# STM32.net
KiCad netlist of a schematic drawn in Altium Designer
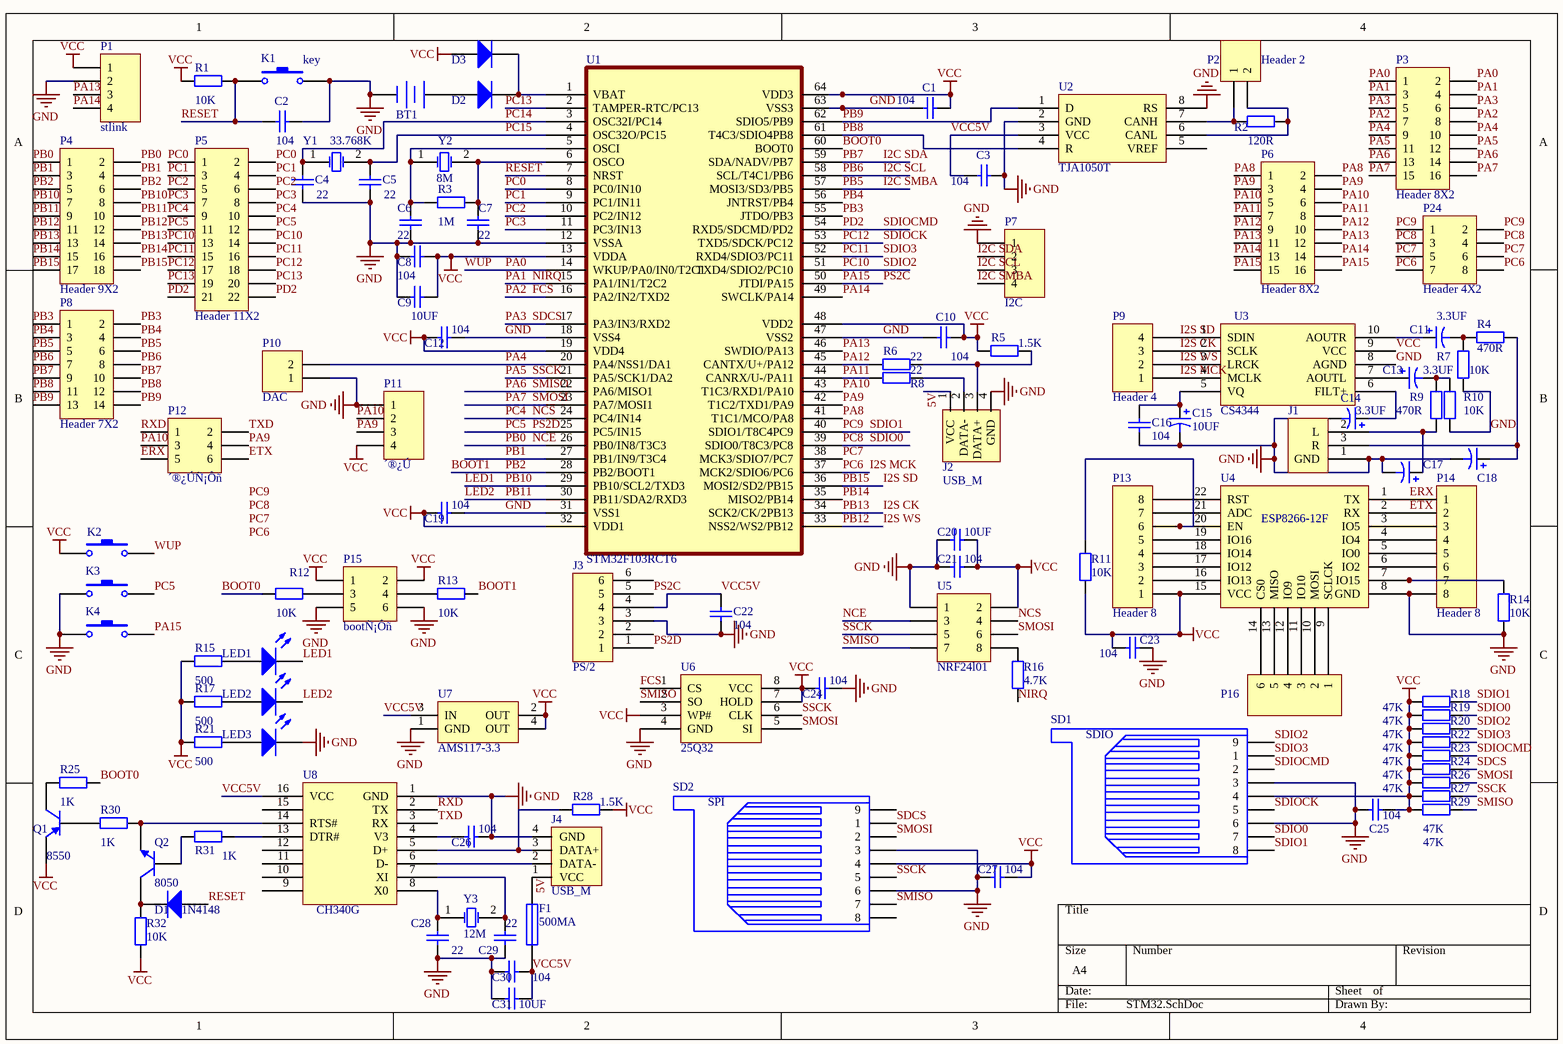
[diagram p0: STM32.SchDoc]

(export (version "E")
  (design (tool "Eeschema 10.0.6"))
  (components
    (comp (ref "BT1") (value "电池") (footprint "电池座") (libsource (lib "SCH封装库") (part "电池")))
    (comp (ref "C1")
      (value "104")
      (footprint "6-0805_N")
      (description "Capacitor")
      (fields (field (name "Comment") "Cap") (field (name "PUBLISHER") "Altium Limited"))
      (libsource (lib "Miscellaneous Devices") (part "Cap"))
    )
    (comp (ref "C2")
      (value "104")
      (footprint "6-0805_N")
      (description "Capacitor")
      (fields (field (name "Comment") "Cap") (field (name "PUBLISHER") "Altium Limited"))
      (libsource (lib "Miscellaneous Devices") (part "Cap"))
    )
    (comp (ref "C3")
      (value "104")
      (footprint "6-0805_N")
      (description "Capacitor")
      (fields (field (name "Comment") "Cap") (field (name "PUBLISHER") "Altium Limited"))
      (libsource (lib "Miscellaneous Devices") (part "Cap"))
    )
    (comp (ref "C4")
      (value "22")
      (footprint "6-0805_N")
      (description "Capacitor")
      (fields (field (name "Comment") "Cap") (field (name "PUBLISHER") "Altium Limited"))
      (libsource (lib "Miscellaneous Devices") (part "Cap"))
    )
    (comp (ref "C5")
      (value "22")
      (footprint "6-0805_N")
      (description "Capacitor")
      (fields (field (name "Comment") "Cap") (field (name "PUBLISHER") "Altium Limited"))
      (libsource (lib "Miscellaneous Devices") (part "Cap"))
    )
    (comp (ref "C6")
      (value "22")
      (footprint "6-0805_N")
      (description "Capacitor")
      (fields (field (name "Comment") "Cap") (field (name "PUBLISHER") "Altium Limited"))
      (libsource (lib "Miscellaneous Devices") (part "Cap"))
    )
    (comp (ref "C7")
      (value "22")
      (footprint "6-0805_N")
      (description "Capacitor")
      (fields (field (name "Comment") "Cap") (field (name "PUBLISHER") "Altium Limited"))
      (libsource (lib "Miscellaneous Devices") (part "Cap"))
    )
    (comp (ref "C8")
      (value "104")
      (footprint "6-0805_N")
      (description "Capacitor")
      (fields (field (name "Comment") "Cap") (field (name "PUBLISHER") "Altium Limited"))
      (libsource (lib "Miscellaneous Devices") (part "Cap"))
    )
    (comp (ref "C9")
      (value "10UF")
      (footprint "6-0805_N")
      (description "Capacitor")
      (fields (field (name "Comment") "Cap") (field (name "PUBLISHER") "Altium Limited"))
      (libsource (lib "Miscellaneous Devices") (part "Cap"))
    )
    (comp (ref "C10")
      (value "104")
      (footprint "6-0805_N")
      (description "Capacitor")
      (fields (field (name "Comment") "Cap") (field (name "PUBLISHER") "Altium Limited"))
      (libsource (lib "Miscellaneous Devices") (part "Cap"))
    )
    (comp (ref "C11")
      (value "3.3UF")
      (footprint "极性电容")
      (description "Polarized Capacitor (Surface Mount)")
      (fields (field (name "Comment") "Cap Pol3") (field (name "PUBLISHER") "Altium Limited"))
      (libsource (lib "Miscellaneous Devices") (part "Cap Pol3"))
    )
    (comp (ref "C12")
      (value "104")
      (footprint "6-0805_N")
      (description "Capacitor")
      (fields (field (name "Comment") "Cap") (field (name "PUBLISHER") "Altium Limited"))
      (libsource (lib "Miscellaneous Devices") (part "Cap"))
    )
    (comp (ref "C13")
      (value "3.3UF")
      (footprint "极性电容")
      (description "Polarized Capacitor (Surface Mount)")
      (fields (field (name "Comment") "Cap Pol3") (field (name "PUBLISHER") "Altium Limited"))
      (libsource (lib "Miscellaneous Devices") (part "Cap Pol3"))
    )
    (comp (ref "C14")
      (value "3.3UF")
      (footprint "极性电容")
      (description "Polarized Capacitor (Surface Mount)")
      (fields (field (name "Comment") "Cap Pol3") (field (name "PUBLISHER") "Altium Limited"))
      (libsource (lib "Miscellaneous Devices") (part "Cap Pol3"))
    )
    (comp (ref "C15")
      (value "10UF")
      (footprint "极性电容")
      (description "Polarized Capacitor (Surface Mount)")
      (fields (field (name "Comment") "Cap Pol3") (field (name "PUBLISHER") "Altium Limited"))
      (libsource (lib "Miscellaneous Devices") (part "Cap Pol3"))
    )
    (comp (ref "C16")
      (value "104")
      (footprint "6-0805_N")
      (description "Capacitor")
      (fields (field (name "Comment") "Cap") (field (name "PUBLISHER") "Altium Limited"))
      (libsource (lib "Miscellaneous Devices") (part "Cap"))
    )
    (comp (ref "C17")
      (value "Cap Pol3")
      (footprint "极性电容")
      (description "Polarized Capacitor (Surface Mount)")
      (fields (field (name "PUBLISHER") "Altium Limited"))
      (libsource (lib "Miscellaneous Devices") (part "Cap Pol3"))
    )
    (comp (ref "C18")
      (value "Cap Pol3")
      (footprint "极性电容")
      (description "Polarized Capacitor (Surface Mount)")
      (fields (field (name "PUBLISHER") "Altium Limited"))
      (libsource (lib "Miscellaneous Devices") (part "Cap Pol3"))
    )
    (comp (ref "C19")
      (value "104")
      (footprint "6-0805_N")
      (description "Capacitor")
      (fields (field (name "Comment") "Cap") (field (name "PUBLISHER") "Altium Limited"))
      (libsource (lib "Miscellaneous Devices") (part "Cap"))
    )
    (comp (ref "C20")
      (value "10UF")
      (footprint "6-0805_N")
      (description "Capacitor")
      (fields (field (name "Comment") "Cap") (field (name "PUBLISHER") "Altium Limited"))
      (libsource (lib "Miscellaneous Devices") (part "Cap"))
    )
    (comp (ref "C21")
      (value "104")
      (footprint "6-0805_N")
      (description "Capacitor")
      (fields (field (name "Comment") "Cap") (field (name "PUBLISHER") "Altium Limited"))
      (libsource (lib "Miscellaneous Devices") (part "Cap"))
    )
    (comp (ref "C22")
      (value "104")
      (footprint "6-0805_N")
      (description "Capacitor")
      (fields (field (name "Comment") "Cap") (field (name "PUBLISHER") "Altium Limited"))
      (libsource (lib "Miscellaneous Devices") (part "Cap"))
    )
    (comp (ref "C23")
      (value "104")
      (footprint "6-0805_N")
      (description "Capacitor")
      (fields (field (name "Comment") "Cap") (field (name "PUBLISHER") "Altium Limited"))
      (libsource (lib "Miscellaneous Devices") (part "Cap"))
    )
    (comp (ref "C24")
      (value "104")
      (footprint "6-0805_N")
      (description "Capacitor")
      (fields (field (name "Comment") "Cap") (field (name "PUBLISHER") "Altium Limited"))
      (libsource (lib "Miscellaneous Devices") (part "Cap"))
    )
    (comp (ref "C25")
      (value "104")
      (footprint "6-0805_N")
      (description "Capacitor")
      (fields (field (name "Comment") "Cap") (field (name "PUBLISHER") "Altium Limited"))
      (libsource (lib "Miscellaneous Devices") (part "Cap"))
    )
    (comp (ref "C26")
      (value "104")
      (footprint "6-0805_N")
      (description "Capacitor")
      (fields (field (name "Comment") "Cap") (field (name "PUBLISHER") "Altium Limited"))
      (libsource (lib "Miscellaneous Devices") (part "Cap"))
    )
    (comp (ref "C27")
      (value "104")
      (footprint "6-0805_N")
      (description "Capacitor")
      (fields (field (name "Comment") "Cap") (field (name "PUBLISHER") "Altium Limited"))
      (libsource (lib "Miscellaneous Devices") (part "Cap"))
    )
    (comp (ref "C28")
      (value "22")
      (footprint "6-0805_N")
      (description "Capacitor")
      (fields (field (name "Comment") "Cap") (field (name "PUBLISHER") "Altium Limited"))
      (libsource (lib "Miscellaneous Devices") (part "Cap"))
    )
    (comp (ref "C29")
      (value "22")
      (footprint "6-0805_N")
      (description "Capacitor")
      (fields (field (name "Comment") "Cap") (field (name "PUBLISHER") "Altium Limited"))
      (libsource (lib "Miscellaneous Devices") (part "Cap"))
    )
    (comp (ref "C30")
      (value "104")
      (footprint "6-0805_N")
      (description "Capacitor")
      (fields (field (name "Comment") "Cap") (field (name "PUBLISHER") "Altium Limited"))
      (libsource (lib "Miscellaneous Devices") (part "Cap"))
    )
    (comp (ref "C31")
      (value "10UF")
      (footprint "6-0805_N")
      (description "Capacitor")
      (fields (field (name "Comment") "Cap") (field (name "PUBLISHER") "Altium Limited"))
      (libsource (lib "Miscellaneous Devices") (part "Cap"))
    )
    (comp (ref "D1")
      (value "1N4148")
      (footprint "1206")
      (description "High Conductance Fast Diode")
      (fields (field (name "PUBLISHER") "Altium Limited"))
      (libsource (lib "Miscellaneous Devices") (part "Diode 1N4148"))
    )
    (comp (ref "D2")
      (value "1N4148")
      (footprint "1206")
      (description "High Conductance Fast Diode")
      (fields (field (name "PUBLISHER") "Altium Limited"))
      (libsource (lib "Miscellaneous Devices") (part "Diode 1N4148"))
    )
    (comp (ref "D3")
      (value "1N4148")
      (footprint "1206")
      (description "High Conductance Fast Diode")
      (fields (field (name "PUBLISHER") "Altium Limited"))
      (libsource (lib "Miscellaneous Devices") (part "Diode 1N4148"))
    )
    (comp (ref "F1")
      (value "500MA")
      (footprint "1812")
      (description "Fuse")
      (fields (field (name "PUBLISHER") "Altium Limited"))
      (libsource (lib "Miscellaneous Devices") (part "Fuse 1"))
    )
    (comp (ref "J1") (value "Component_1") (footprint "耳机座") (libsource (lib "耳机") (part "Component_1")))
    (comp (ref "J2") (value "USB_M") (footprint "USB MICRO") (libsource (lib "") (part "USB_M_1")))
    (comp (ref "J3") (value "PS/2") (footprint "PS/2") (libsource (lib "SCH封装库") (part "PS/2")))
    (comp (ref "J4") (value "USB_M") (footprint "USB MICRO") (libsource (lib "SCH封装库") (part "USB_M")))
    (comp (ref "K1") (value "key") (footprint "按键") (libsource (lib "SCH封装库") (part "按键")))
    (comp (ref "K2") (value "按键") (footprint "按键") (libsource (lib "SCH封装库") (part "按键")))
    (comp (ref "K3") (value "按键") (footprint "按键") (libsource (lib "SCH封装库") (part "按键")))
    (comp (ref "K4") (value "按键") (footprint "按键") (libsource (lib "SCH封装库") (part "按键")))
    (comp (ref "LED1") (value "LED") (footprint "6-0805_N") (libsource (lib "SCH封装库") (part "发光二极管")))
    (comp (ref "LED2") (value "LED") (footprint "6-0805_N") (libsource (lib "SCH封装库") (part "发光二极管")))
    (comp (ref "LED3") (value "LED") (footprint "6-0805_N") (libsource (lib "SCH封装库") (part "发光二极管")))
    (comp (ref "P1")
      (value "stlink")
      (footprint "HDR1X4")
      (description "Header, 4-Pin")
      (fields (field (name "PUBLISHER") "Altium Limited"))
      (libsource (lib "") (part "Header 4_1"))
    )
    (comp (ref "P2")
      (value "Header 2")
      (footprint "HDR1X2")
      (description "Header, 2-Pin")
      (fields (field (name "PUBLISHER") "Altium Limited"))
      (libsource (lib "") (part "Header 2_1"))
    )
    (comp (ref "P3")
      (value "Header 8X2")
      (footprint "HDR2X8")
      (description "Header, 8-Pin, Dual row")
      (fields (field (name "PUBLISHER") "Altium Limited"))
      (libsource (lib "Miscellaneous Connectors") (part "Header 8X2"))
    )
    (comp (ref "P4")
      (value "Header 9X2")
      (footprint "HDR2X9")
      (description "Header, 9-Pin, Dual row")
      (fields (field (name "PUBLISHER") "Altium Limited"))
      (libsource (lib "Miscellaneous Connectors") (part "Header 9X2"))
    )
    (comp (ref "P5")
      (value "Header 11X2")
      (footprint "HDR2X11")
      (description "Header, 11-Pin, Dual row")
      (fields (field (name "PUBLISHER") "Altium Limited"))
      (libsource (lib "Miscellaneous Connectors") (part "Header 11X2"))
    )
    (comp (ref "P6")
      (value "Header 8X2")
      (footprint "HDR2X8")
      (description "Header, 8-Pin, Dual row")
      (fields (field (name "PUBLISHER") "Altium Limited"))
      (libsource (lib "Miscellaneous Connectors") (part "Header 8X2"))
    )
    (comp (ref "P7")
      (value "I2C")
      (footprint "HDR1X4")
      (description "Header, 4-Pin")
      (fields (field (name "PUBLISHER") "Altium Limited"))
      (libsource (lib "") (part "Header 4_1"))
    )
    (comp (ref "P8")
      (value "Header 7X2")
      (footprint "HDR2X7")
      (description "Header, 7-Pin, Dual row")
      (fields (field (name "PUBLISHER") "Altium Limited"))
      (libsource (lib "Miscellaneous Connectors") (part "Header 7X2"))
    )
    (comp (ref "P9")
      (value "Header 4")
      (footprint "HDR1X4")
      (description "Header, 4-Pin")
      (fields (field (name "PUBLISHER") "Altium Limited"))
      (libsource (lib "Miscellaneous Connectors") (part "Header 4"))
    )
    (comp (ref "P10")
      (value "DAC")
      (footprint "HDR1X2")
      (description "Header, 2-Pin")
      (fields (field (name "PUBLISHER") "Altium Limited"))
      (libsource (lib "Miscellaneous Connectors") (part "Header 2"))
    )
    (comp (ref "P11")
      (value "串口")
      (footprint "HDR1X4")
      (description "Header, 4-Pin")
      (fields (field (name "PUBLISHER") "Altium Limited"))
      (libsource (lib "") (part "Header 4_1"))
    )
    (comp (ref "P12")
      (value "串口选择")
      (footprint "HDR2X3")
      (description "Header, 3-Pin, Dual row")
      (fields (field (name "PUBLISHER") "Altium Limited"))
      (libsource (lib "Miscellaneous Connectors") (part "Header 3X2"))
    )
    (comp (ref "P13")
      (value "Header 8")
      (footprint "HDR1X8")
      (description "Header, 8-Pin")
      (fields (field (name "PUBLISHER") "Altium Limited"))
      (libsource (lib "") (part "Header 8_1"))
    )
    (comp (ref "P14")
      (value "Header 8")
      (footprint "HDR1X8")
      (description "Header, 8-Pin")
      (fields (field (name "PUBLISHER") "Altium Limited"))
      (libsource (lib "Miscellaneous Connectors") (part "Header 8"))
    )
    (comp (ref "P15")
      (value "boot选择")
      (footprint "HDR2X3")
      (description "Header, 3-Pin, Dual row")
      (fields (field (name "PUBLISHER") "Altium Limited"))
      (libsource (lib "Miscellaneous Connectors") (part "Header 3X2"))
    )
    (comp (ref "P16")
      (value "Header 6")
      (footprint "HDR1X6")
      (description "Header, 6-Pin")
      (fields (field (name "PUBLISHER") "Altium Limited"))
      (libsource (lib "Miscellaneous Connectors") (part "Header 6"))
    )
    (comp (ref "P24")
      (value "Header 4X2")
      (footprint "HDR2X4")
      (description "Header, 4-Pin, Dual row")
      (fields (field (name "PUBLISHER") "Altium Limited"))
      (libsource (lib "Miscellaneous Connectors") (part "Header 4X2"))
    )
    (comp (ref "Q1")
      (value "8550")
      (footprint "SOT-23B_N")
      (description "PNP Bipolar Transistor")
      (fields (field (name "PUBLISHER") "Altium Limited"))
      (libsource (lib "Miscellaneous Devices") (part "PNP"))
    )
    (comp (ref "Q2")
      (value "8050")
      (footprint "SOT-23B_N")
      (description "NPN Bipolar Transistor")
      (fields (field (name "PUBLISHER") "Altium Limited"))
      (libsource (lib "Miscellaneous Devices") (part "NPN"))
    )
    (comp (ref "R1")
      (value "10K")
      (footprint "6-0805_N")
      (description "Resistor")
      (fields (field (name "Comment") "Res2") (field (name "PUBLISHER") "Altium Limited"))
      (libsource (lib "Miscellaneous Devices") (part "Res2"))
    )
    (comp (ref "R2")
      (value "120R")
      (footprint "6-0805_N")
      (description "Resistor")
      (fields (field (name "Comment") "Res2") (field (name "PUBLISHER") "Altium Limited"))
      (libsource (lib "Miscellaneous Devices") (part "Res2"))
    )
    (comp (ref "R3")
      (value "1M")
      (footprint "6-0805_N")
      (description "Resistor")
      (fields (field (name "Comment") "Res2") (field (name "PUBLISHER") "Altium Limited"))
      (libsource (lib "Miscellaneous Devices") (part "Res2"))
    )
    (comp (ref "R4")
      (value "470R")
      (footprint "6-0805_N")
      (description "Resistor")
      (fields (field (name "Comment") "Res2") (field (name "PUBLISHER") "Altium Limited"))
      (libsource (lib "") (part "Res2_3"))
    )
    (comp (ref "R5")
      (value "1.5K")
      (footprint "6-0805_N")
      (description "Resistor")
      (fields (field (name "Comment") "Res2") (field (name "PUBLISHER") "Altium Limited"))
      (libsource (lib "Miscellaneous Devices") (part "Res2"))
    )
    (comp (ref "R6")
      (value "22")
      (footprint "6-0805_N")
      (description "Resistor")
      (fields (field (name "Comment") "Res2") (field (name "PUBLISHER") "Altium Limited"))
      (libsource (lib "Miscellaneous Devices") (part "Res2"))
    )
    (comp (ref "R7")
      (value "10K")
      (footprint "6-0805_N")
      (description "Resistor")
      (fields (field (name "Comment") "Res2") (field (name "PUBLISHER") "Altium Limited"))
      (libsource (lib "") (part "Res2_1"))
    )
    (comp (ref "R8")
      (value "22")
      (footprint "6-0805_N")
      (description "Resistor")
      (fields (field (name "Comment") "Res2") (field (name "PUBLISHER") "Altium Limited"))
      (libsource (lib "Miscellaneous Devices") (part "Res2"))
    )
    (comp (ref "R9")
      (value "470R")
      (footprint "6-0805_N")
      (description "Resistor")
      (fields (field (name "Comment") "Res2") (field (name "PUBLISHER") "Altium Limited"))
      (libsource (lib "") (part "Res2_2"))
    )
    (comp (ref "R10")
      (value "10K")
      (footprint "6-0805_N")
      (description "Resistor")
      (fields (field (name "Comment") "Res2") (field (name "PUBLISHER") "Altium Limited"))
      (libsource (lib "") (part "Res2_1"))
    )
    (comp (ref "R11")
      (value "10K")
      (footprint "6-0805_N")
      (description "Resistor")
      (fields (field (name "Comment") "Res2") (field (name "PUBLISHER") "Altium Limited"))
      (libsource (lib "") (part "Res2_1"))
    )
    (comp (ref "R12")
      (value "10K")
      (footprint "6-0805_N")
      (description "Resistor")
      (fields (field (name "Comment") "Res2") (field (name "PUBLISHER") "Altium Limited"))
      (libsource (lib "Miscellaneous Devices") (part "Res2"))
    )
    (comp (ref "R13")
      (value "10K")
      (footprint "6-0805_N")
      (description "Resistor")
      (fields (field (name "Comment") "Res2") (field (name "PUBLISHER") "Altium Limited"))
      (libsource (lib "Miscellaneous Devices") (part "Res2"))
    )
    (comp (ref "R14")
      (value "10K")
      (footprint "6-0805_N")
      (description "Resistor")
      (fields (field (name "Comment") "Res2") (field (name "PUBLISHER") "Altium Limited"))
      (libsource (lib "") (part "Res2_1"))
    )
    (comp (ref "R15")
      (value "500")
      (footprint "6-0805_N")
      (description "Resistor")
      (fields (field (name "Comment") "Res2") (field (name "PUBLISHER") "Altium Limited"))
      (libsource (lib "Miscellaneous Devices") (part "Res2"))
    )
    (comp (ref "R16")
      (value "4.7K")
      (footprint "6-0805_N")
      (description "Resistor")
      (fields (field (name "Comment") "Res2") (field (name "PUBLISHER") "Altium Limited"))
      (libsource (lib "") (part "Res2_2"))
    )
    (comp (ref "R17")
      (value "500")
      (footprint "6-0805_N")
      (description "Resistor")
      (fields (field (name "Comment") "Res2") (field (name "PUBLISHER") "Altium Limited"))
      (libsource (lib "Miscellaneous Devices") (part "Res2"))
    )
    (comp (ref "R18")
      (value "47K")
      (footprint "6-0805_N")
      (description "Resistor")
      (fields (field (name "Comment") "Res2") (field (name "PUBLISHER") "Altium Limited"))
      (libsource (lib "Miscellaneous Devices") (part "Res2"))
    )
    (comp (ref "R19")
      (value "47K")
      (footprint "6-0805_N")
      (description "Resistor")
      (fields (field (name "Comment") "Res2") (field (name "PUBLISHER") "Altium Limited"))
      (libsource (lib "Miscellaneous Devices") (part "Res2"))
    )
    (comp (ref "R20")
      (value "47K")
      (footprint "6-0805_N")
      (description "Resistor")
      (fields (field (name "Comment") "Res2") (field (name "PUBLISHER") "Altium Limited"))
      (libsource (lib "Miscellaneous Devices") (part "Res2"))
    )
    (comp (ref "R21")
      (value "500")
      (footprint "6-0805_N")
      (description "Resistor")
      (fields (field (name "Comment") "Res2") (field (name "PUBLISHER") "Altium Limited"))
      (libsource (lib "Miscellaneous Devices") (part "Res2"))
    )
    (comp (ref "R22")
      (value "47K")
      (footprint "6-0805_N")
      (description "Resistor")
      (fields (field (name "Comment") "Res2") (field (name "PUBLISHER") "Altium Limited"))
      (libsource (lib "Miscellaneous Devices") (part "Res2"))
    )
    (comp (ref "R23")
      (value "47K")
      (footprint "6-0805_N")
      (description "Resistor")
      (fields (field (name "Comment") "Res2") (field (name "PUBLISHER") "Altium Limited"))
      (libsource (lib "Miscellaneous Devices") (part "Res2"))
    )
    (comp (ref "R24")
      (value "47K")
      (footprint "6-0805_N")
      (description "Resistor")
      (fields (field (name "Comment") "Res2") (field (name "PUBLISHER") "Altium Limited"))
      (libsource (lib "Miscellaneous Devices") (part "Res2"))
    )
    (comp (ref "R25")
      (value "1K")
      (footprint "6-0805_N")
      (description "Resistor")
      (fields (field (name "Comment") "Res2") (field (name "PUBLISHER") "Altium Limited"))
      (libsource (lib "Miscellaneous Devices") (part "Res2"))
    )
    (comp (ref "R26")
      (value "47K")
      (footprint "6-0805_N")
      (description "Resistor")
      (fields (field (name "Comment") "Res2") (field (name "PUBLISHER") "Altium Limited"))
      (libsource (lib "Miscellaneous Devices") (part "Res2"))
    )
    (comp (ref "R27")
      (value "47K")
      (footprint "6-0805_N")
      (description "Resistor")
      (fields (field (name "Comment") "Res2") (field (name "PUBLISHER") "Altium Limited"))
      (libsource (lib "Miscellaneous Devices") (part "Res2"))
    )
    (comp (ref "R28")
      (value "1.5K")
      (footprint "6-0805_N")
      (description "Resistor")
      (fields (field (name "Comment") "Res2") (field (name "PUBLISHER") "Altium Limited"))
      (libsource (lib "Miscellaneous Devices") (part "Res2"))
    )
    (comp (ref "R29")
      (value "47K")
      (footprint "6-0805_N")
      (description "Resistor")
      (fields (field (name "Comment") "Res2") (field (name "PUBLISHER") "Altium Limited"))
      (libsource (lib "Miscellaneous Devices") (part "Res2"))
    )
    (comp (ref "R30")
      (value "1K")
      (footprint "6-0805_N")
      (description "Resistor")
      (fields (field (name "Comment") "Res2") (field (name "PUBLISHER") "Altium Limited"))
      (libsource (lib "Miscellaneous Devices") (part "Res2"))
    )
    (comp (ref "R31")
      (value "1K")
      (footprint "6-0805_N")
      (description "Resistor")
      (fields (field (name "Comment") "Res2") (field (name "PUBLISHER") "Altium Limited"))
      (libsource (lib "Miscellaneous Devices") (part "Res2"))
    )
    (comp (ref "R32")
      (value "10K")
      (footprint "6-0805_N")
      (description "Resistor")
      (fields (field (name "Comment") "Res2") (field (name "PUBLISHER") "Altium Limited"))
      (libsource (lib "") (part "Res2_1"))
    )
    (comp (ref "SD1")
      (value "PJS008-2000")
      (footprint "TFCARD-M")
      (fields (field (name "A") "SDIO"))
      (libsource (lib "MB525") (part "SMS016AFA5E"))
    )
    (comp (ref "SD2")
      (value "PJS008-2000")
      (footprint "SDCARD_A")
      (fields (field (name "A") "SPI"))
      (libsource (lib "MB525") (part "SMS016AFA5E"))
    )
    (comp (ref "U1")
      (value "STM32F103RCT6")
      (footprint "LQFP64")
      (libsource (lib "STM32SCH") (part "STM32F103RDT6"))
    )
    (comp (ref "U2") (value "TJA1050T") (footprint "SO8_M") (libsource (lib "TJA1050") (part "Component_1")))
    (comp (ref "U3")
      (value "CS4344")
      (footprint "TSSOP110_s")
      (libsource (lib "CS4344") (part "Component_1"))
    )
    (comp (ref "U4")
      (value "Component_1")
      (footprint "ESP_12_f")
      (libsource (lib "ESP8266") (part "Component_1"))
    )
    (comp (ref "U5")
      (value "NRF24l01")
      (footprint "HDR2X4")
      (description "Header, 4-Pin, Dual row")
      (fields (field (name "PUBLISHER") "Altium Limited"))
      (libsource (lib "Miscellaneous Connectors") (part "Header 4X2"))
    )
    (comp (ref "U6") (value "25Q32") (footprint "SO8_M") (libsource (lib "25Q32") (part "Component_1")))
    (comp (ref "U7")
      (value "AMS117-3.3")
      (footprint "ZZ311")
      (description "800mA and 1A Low Dropout Positive Regulator 2.85V, 3.3V, 5V, and Adjustable")
      (fields (field (name "PUBLISHER") "Altium Limited"))
      (libsource (lib "BB Power Mgt Voltage Regulator") (part "REG1117-3.3"))
    )
    (comp (ref "U8")
      (value "Component_1")
      (footprint "SO-16_M")
      (libsource (lib "CH340") (part "Component_1"))
    )
    (comp (ref "Y1") (value "33.768K") (footprint "SIP2") (libsource (lib "SCH封装库") (part "晶振")))
    (comp (ref "Y2") (value "8M") (footprint "晶振") (libsource (lib "SCH封装库") (part "晶振")))
    (comp (ref "Y3") (value "12M") (footprint "晶振") (libsource (lib "SCH封装库") (part "晶振")))
  )
  (nets
    (net (code "1") (name "/5V") (class "Default")
      (node (ref "F1") (pin "2") (pinfunction "2_2") (pintype "passive"))
      (node (ref "J2") (pin "1") (pinfunction "VCC_1") (pintype "passive"))
      (node (ref "J4") (pin "1") (pinfunction "VCC_1") (pintype "passive"))
    )
    (net (code "2") (name "/BOOT0") (class "Default")
      (node (ref "R12") (pin "1") (pinfunction "1_1") (pintype "passive"))
      (node (ref "R25") (pin "2") (pinfunction "2_2") (pintype "passive"))
      (node (ref "U1") (pin "60") (pinfunction "BOOT0_60") (pintype "passive"))
    )
    (net (code "3") (name "/BOOT1") (class "Default")
      (node (ref "P4") (pin "5") (pinfunction "5_5") (pintype "passive"))
      (node (ref "P4") (pin "6") (pinfunction "6_6") (pintype "passive"))
      (node (ref "R13") (pin "2") (pinfunction "2_2") (pintype "passive"))
      (node (ref "U1") (pin "28") (pinfunction "PB2/BOOT1_28") (pintype "passive"))
    )
    (net (code "4") (name "/ERX") (class "Default")
      (node (ref "P12") (pin "5") (pinfunction "5_5") (pintype "passive"))
      (node (ref "P14") (pin "1") (pinfunction "1_1") (pintype "passive"))
      (node (ref "U4") (pin "1") (pinfunction "TX_1") (pintype "passive"))
    )
    (net (code "5") (name "/ETX") (class "Default")
      (node (ref "P12") (pin "6") (pinfunction "6_6") (pintype "passive"))
      (node (ref "P14") (pin "2") (pinfunction "2_2") (pintype "passive"))
      (node (ref "U4") (pin "2") (pinfunction "RX_2") (pintype "passive"))
    )
    (net (code "6") (name "/FCS") (class "Default")
      (node (ref "P3") (pin "7") (pinfunction "7_7") (pintype "passive"))
      (node (ref "P3") (pin "8") (pinfunction "8_8") (pintype "passive"))
      (node (ref "U1") (pin "16") (pinfunction "PA2/IN2/TXD2_16") (pintype "passive"))
      (node (ref "U6") (pin "1") (pinfunction "CS_1") (pintype "passive"))
    )
    (net (code "7") (name "/I2C SCL") (class "Default")
      (node (ref "P7") (pin "3") (pinfunction "3_3") (pintype "passive"))
      (node (ref "P8") (pin "7") (pinfunction "7_7") (pintype "passive"))
      (node (ref "P8") (pin "8") (pinfunction "8_8") (pintype "passive"))
      (node (ref "U1") (pin "58") (pinfunction "SCL/T4C1/PB6_58") (pintype "passive"))
    )
    (net (code "8") (name "/I2C SDA") (class "Default")
      (node (ref "P7") (pin "2") (pinfunction "2_2") (pintype "passive"))
      (node (ref "P8") (pin "10") (pinfunction "10_10") (pintype "passive"))
      (node (ref "P8") (pin "9") (pinfunction "9_9") (pintype "passive"))
      (node (ref "U1") (pin "59") (pinfunction "SDA/NADV/PB7_59") (pintype "passive"))
    )
    (net (code "9") (name "/I2C SMBA") (class "Default")
      (node (ref "P7") (pin "4") (pinfunction "4_4") (pintype "passive"))
      (node (ref "P8") (pin "5") (pinfunction "5_5") (pintype "passive"))
      (node (ref "P8") (pin "6") (pinfunction "6_6") (pintype "passive"))
      (node (ref "U1") (pin "57") (pinfunction "MOSI3/SD3/PB5_57") (pintype "passive"))
    )
    (net (code "10") (name "/I2S CK") (class "Default")
      (node (ref "P4") (pin "13") (pinfunction "13_13") (pintype "passive"))
      (node (ref "P4") (pin "14") (pinfunction "14_14") (pintype "passive"))
      (node (ref "P9") (pin "3") (pinfunction "3_3") (pintype "passive"))
      (node (ref "U1") (pin "34") (pinfunction "SCK2/CK/2PB13_34") (pintype "passive"))
      (node (ref "U3") (pin "2") (pinfunction "SCLK_2") (pintype "passive"))
    )
    (net (code "11") (name "/I2S MCK") (class "Default")
      (node (ref "P24") (pin "7") (pinfunction "7_7") (pintype "passive"))
      (node (ref "P24") (pin "8") (pinfunction "8_8") (pintype "passive"))
      (node (ref "P9") (pin "1") (pinfunction "1_1") (pintype "passive"))
      (node (ref "U1") (pin "37") (pinfunction "MCK2/SDIO6/PC6_37") (pintype "passive"))
      (node (ref "U3") (pin "4") (pinfunction "MCLK_4") (pintype "passive"))
    )
    (net (code "12") (name "/I2S SD") (class "Default")
      (node (ref "P4") (pin "17") (pinfunction "17_17") (pintype "passive"))
      (node (ref "P4") (pin "18") (pinfunction "18_18") (pintype "passive"))
      (node (ref "P9") (pin "4") (pinfunction "4_4") (pintype "passive"))
      (node (ref "U1") (pin "36") (pinfunction "MOSI2/SD2/PB15_36") (pintype "passive"))
      (node (ref "U3") (pin "1") (pinfunction "SDIN_1") (pintype "passive"))
    )
    (net (code "13") (name "/I2S WS") (class "Default")
      (node (ref "P4") (pin "11") (pinfunction "11_11") (pintype "passive"))
      (node (ref "P4") (pin "12") (pinfunction "12_12") (pintype "passive"))
      (node (ref "P9") (pin "2") (pinfunction "2_2") (pintype "passive"))
      (node (ref "U1") (pin "33") (pinfunction "NSS2/WS2/PB12_33") (pintype "passive"))
      (node (ref "U3") (pin "3") (pinfunction "LRCK_3") (pintype "passive"))
    )
    (net (code "14") (name "/LED1") (class "Default")
      (node (ref "LED1") (pin "2") (pinfunction "2_2") (pintype "passive"))
      (node (ref "P4") (pin "7") (pinfunction "7_7") (pintype "passive"))
      (node (ref "P4") (pin "8") (pinfunction "8_8") (pintype "passive"))
      (node (ref "U1") (pin "29") (pinfunction "PB10/SCL2/TXD3_29") (pintype "passive"))
    )
    (net (code "15") (name "/LED2") (class "Default")
      (node (ref "LED2") (pin "2") (pinfunction "2_2") (pintype "passive"))
      (node (ref "P4") (pin "10") (pinfunction "10_10") (pintype "passive"))
      (node (ref "P4") (pin "9") (pinfunction "9_9") (pintype "passive"))
      (node (ref "U1") (pin "30") (pinfunction "PB11/SDA2/RXD3_30") (pintype "passive"))
    )
    (net (code "16") (name "/NCE") (class "Default")
      (node (ref "P4") (pin "1") (pinfunction "1_1") (pintype "passive"))
      (node (ref "P4") (pin "2") (pinfunction "2_2") (pintype "passive"))
      (node (ref "U1") (pin "26") (pinfunction "PB0/IN8/T3C3_26") (pintype "passive"))
      (node (ref "U5") (pin "3") (pinfunction "3_3") (pintype "passive"))
    )
    (net (code "17") (name "/NCS") (class "Default")
      (node (ref "P5") (pin "10") (pinfunction "10_10") (pintype "passive"))
      (node (ref "P5") (pin "9") (pinfunction "9_9") (pintype "passive"))
      (node (ref "U1") (pin "24") (pinfunction "PC4/IN14_24") (pintype "passive"))
      (node (ref "U5") (pin "4") (pinfunction "4_4") (pintype "passive"))
    )
    (net (code "18") (name "/NIRQ") (class "Default")
      (node (ref "P3") (pin "3") (pinfunction "3_3") (pintype "passive"))
      (node (ref "P3") (pin "4") (pinfunction "4_4") (pintype "passive"))
      (node (ref "R16") (pin "2") (pinfunction "2_2") (pintype "passive"))
      (node (ref "U1") (pin "15") (pinfunction "PA1/IN1/T2C2_15") (pintype "passive"))
    )
    (net (code "19") (name "/PA0") (class "Default")
      (node (ref "K2") (pin "2") (pinfunction "2_2") (pintype "passive"))
      (node (ref "P3") (pin "1") (pinfunction "1_1") (pintype "passive"))
      (node (ref "P3") (pin "2") (pinfunction "2_2") (pintype "passive"))
      (node (ref "U1") (pin "14") (pinfunction "WKUP/PA0/IN0/T2C1_14") (pintype "passive"))
    )
    (net (code "20") (name "/PA3") (class "Default")
      (node (ref "P3") (pin "5") (pinfunction "5_5") (pintype "passive"))
      (node (ref "P3") (pin "6") (pinfunction "6_6") (pintype "passive"))
      (node (ref "R24") (pin "2") (pinfunction "2_2") (pintype "passive"))
      (node (ref "SD2") (pin "1") (pinfunction "1_1") (pintype "passive"))
      (node (ref "U1") (pin "17") (pinfunction "PA3/IN3/RXD2_17") (pintype "passive"))
    )
    (net (code "21") (name "/PA4") (class "Default")
      (node (ref "P10") (pin "2") (pinfunction "2_2") (pintype "passive"))
      (node (ref "P3") (pin "10") (pinfunction "10_10") (pintype "passive"))
      (node (ref "P3") (pin "9") (pinfunction "9_9") (pintype "passive"))
      (node (ref "U1") (pin "20") (pinfunction "PA4/NSS1/DA1_20") (pintype "passive"))
    )
    (net (code "22") (name "/PA5") (class "Default")
      (node (ref "P3") (pin "11") (pinfunction "11_11") (pintype "passive"))
      (node (ref "P3") (pin "12") (pinfunction "12_12") (pintype "passive"))
      (node (ref "R27") (pin "2") (pinfunction "2_2") (pintype "passive"))
      (node (ref "SD2") (pin "5") (pinfunction "5_5") (pintype "passive"))
      (node (ref "U1") (pin "21") (pinfunction "PA5/SCK1/DA2_21") (pintype "passive"))
      (node (ref "U5") (pin "5") (pinfunction "5_5") (pintype "passive"))
      (node (ref "U6") (pin "6") (pinfunction "CLK_6") (pintype "passive"))
    )
    (net (code "23") (name "/PA6") (class "Default")
      (node (ref "P3") (pin "13") (pinfunction "13_13") (pintype "passive"))
      (node (ref "P3") (pin "14") (pinfunction "14_14") (pintype "passive"))
      (node (ref "R29") (pin "2") (pinfunction "2_2") (pintype "passive"))
      (node (ref "SD2") (pin "7") (pinfunction "7_7") (pintype "passive"))
      (node (ref "U1") (pin "22") (pinfunction "PA6/MISO1_22") (pintype "passive"))
      (node (ref "U5") (pin "7") (pinfunction "7_7") (pintype "passive"))
      (node (ref "U6") (pin "2") (pinfunction "SO_2") (pintype "passive"))
    )
    (net (code "24") (name "/PA7") (class "Default")
      (node (ref "P3") (pin "15") (pinfunction "15_15") (pintype "passive"))
      (node (ref "P3") (pin "16") (pinfunction "16_16") (pintype "passive"))
      (node (ref "R26") (pin "2") (pinfunction "2_2") (pintype "passive"))
      (node (ref "SD2") (pin "2") (pinfunction "2_2") (pintype "passive"))
      (node (ref "U1") (pin "23") (pinfunction "PA7/MOSI1_23") (pintype "passive"))
      (node (ref "U5") (pin "6") (pinfunction "6_6") (pintype "passive"))
      (node (ref "U6") (pin "5") (pinfunction "SI_5") (pintype "passive"))
    )
    (net (code "25") (name "/PA8") (class "Default")
      (node (ref "P6") (pin "1") (pinfunction "1_1") (pintype "passive"))
      (node (ref "P6") (pin "2") (pinfunction "2_2") (pintype "passive"))
      (node (ref "U1") (pin "41") (pinfunction "T1C1/MCO/PA8_41") (pintype "passive"))
    )
    (net (code "26") (name "/PA9") (class "Default")
      (node (ref "P11") (pin "3") (pinfunction "3_3") (pintype "passive"))
      (node (ref "P12") (pin "4") (pinfunction "4_4") (pintype "passive"))
      (node (ref "P6") (pin "3") (pinfunction "3_3") (pintype "passive"))
      (node (ref "P6") (pin "4") (pinfunction "4_4") (pintype "passive"))
      (node (ref "U1") (pin "42") (pinfunction "T1C2/TXD1/PA9_42") (pintype "passive"))
    )
    (net (code "27") (name "/PA10") (class "Default")
      (node (ref "P11") (pin "2") (pinfunction "2_2") (pintype "passive"))
      (node (ref "P12") (pin "3") (pinfunction "3_3") (pintype "passive"))
      (node (ref "P6") (pin "5") (pinfunction "5_5") (pintype "passive"))
      (node (ref "P6") (pin "6") (pinfunction "6_6") (pintype "passive"))
      (node (ref "U1") (pin "43") (pinfunction "T1C3/RXD1/PA10_43") (pintype "passive"))
    )
    (net (code "28") (name "/PA11") (class "Default")
      (node (ref "P6") (pin "7") (pinfunction "7_7") (pintype "passive"))
      (node (ref "P6") (pin "8") (pinfunction "8_8") (pintype "passive"))
      (node (ref "R8") (pin "1") (pinfunction "1_1") (pintype "passive"))
      (node (ref "U1") (pin "44") (pinfunction "CANRX/U-/PA11_44") (pintype "passive"))
    )
    (net (code "29") (name "/PA12") (class "Default")
      (node (ref "P6") (pin "10") (pinfunction "10_10") (pintype "passive"))
      (node (ref "P6") (pin "9") (pinfunction "9_9") (pintype "passive"))
      (node (ref "R6") (pin "1") (pinfunction "1_1") (pintype "passive"))
      (node (ref "U1") (pin "45") (pinfunction "CANTX/U+/PA12_45") (pintype "passive"))
    )
    (net (code "30") (name "/PA13") (class "Default")
      (node (ref "P1") (pin "3") (pinfunction "3_3") (pintype "passive"))
      (node (ref "P6") (pin "11") (pinfunction "11_11") (pintype "passive"))
      (node (ref "P6") (pin "12") (pinfunction "12_12") (pintype "passive"))
      (node (ref "U1") (pin "46") (pinfunction "SWDIO/PA13_46") (pintype "passive"))
    )
    (net (code "31") (name "/PA14") (class "Default")
      (node (ref "P1") (pin "4") (pinfunction "4_4") (pintype "passive"))
      (node (ref "P6") (pin "13") (pinfunction "13_13") (pintype "passive"))
      (node (ref "P6") (pin "14") (pinfunction "14_14") (pintype "passive"))
      (node (ref "U1") (pin "49") (pinfunction "SWCLK/PA14_49") (pintype "passive"))
    )
    (net (code "32") (name "/PA15") (class "Default")
      (node (ref "J3") (pin "5") (pinfunction "5_5") (pintype "passive"))
      (node (ref "K4") (pin "2") (pinfunction "2_2") (pintype "passive"))
      (node (ref "P6") (pin "15") (pinfunction "15_15") (pintype "passive"))
      (node (ref "P6") (pin "16") (pinfunction "16_16") (pintype "passive"))
      (node (ref "U1") (pin "50") (pinfunction "JTDI/PA15_50") (pintype "passive"))
    )
    (net (code "33") (name "/PB1") (class "Default")
      (node (ref "P4") (pin "3") (pinfunction "3_3") (pintype "passive"))
      (node (ref "P4") (pin "4") (pinfunction "4_4") (pintype "passive"))
      (node (ref "U1") (pin "27") (pinfunction "PB1/IN9/T3C4_27") (pintype "passive"))
    )
    (net (code "34") (name "/PB3") (class "Default")
      (node (ref "P8") (pin "1") (pinfunction "1_1") (pintype "passive"))
      (node (ref "P8") (pin "2") (pinfunction "2_2") (pintype "passive"))
      (node (ref "U1") (pin "55") (pinfunction "JTDO/PB3_55") (pintype "passive"))
    )
    (net (code "35") (name "/PB4") (class "Default")
      (node (ref "P8") (pin "3") (pinfunction "3_3") (pintype "passive"))
      (node (ref "P8") (pin "4") (pinfunction "4_4") (pintype "passive"))
      (node (ref "U1") (pin "56") (pinfunction "JNTRST/PB4_56") (pintype "passive"))
    )
    (net (code "36") (name "/PB8") (class "Default")
      (node (ref "P8") (pin "11") (pinfunction "11_11") (pintype "passive"))
      (node (ref "P8") (pin "12") (pinfunction "12_12") (pintype "passive"))
      (node (ref "U1") (pin "61") (pinfunction "T4C3/SDIO4PB8_61") (pintype "passive"))
      (node (ref "U2") (pin "4") (pinfunction "R_4") (pintype "passive"))
    )
    (net (code "37") (name "/PB9") (class "Default")
      (node (ref "P8") (pin "13") (pinfunction "13_13") (pintype "passive"))
      (node (ref "P8") (pin "14") (pinfunction "14_14") (pintype "passive"))
      (node (ref "U1") (pin "62") (pinfunction "SDIO5/PB9_62") (pintype "passive"))
      (node (ref "U2") (pin "1") (pinfunction "D_1") (pintype "passive"))
    )
    (net (code "38") (name "/PB14") (class "Default")
      (node (ref "P4") (pin "15") (pinfunction "15_15") (pintype "passive"))
      (node (ref "P4") (pin "16") (pinfunction "16_16") (pintype "passive"))
      (node (ref "U1") (pin "35") (pinfunction "MISO2/PB14_35") (pintype "passive"))
    )
    (net (code "39") (name "/PC0") (class "Default")
      (node (ref "P5") (pin "1") (pinfunction "1_1") (pintype "passive"))
      (node (ref "P5") (pin "2") (pinfunction "2_2") (pintype "passive"))
      (node (ref "U1") (pin "8") (pinfunction "PC0/IN10_8") (pintype "passive"))
    )
    (net (code "40") (name "/PC1") (class "Default")
      (node (ref "P5") (pin "3") (pinfunction "3_3") (pintype "passive"))
      (node (ref "P5") (pin "4") (pinfunction "4_4") (pintype "passive"))
      (node (ref "U1") (pin "9") (pinfunction "PC1/IN11_9") (pintype "passive"))
    )
    (net (code "41") (name "/PC2") (class "Default")
      (node (ref "P5") (pin "5") (pinfunction "5_5") (pintype "passive"))
      (node (ref "P5") (pin "6") (pinfunction "6_6") (pintype "passive"))
      (node (ref "U1") (pin "10") (pinfunction "PC2/IN12_10") (pintype "passive"))
    )
    (net (code "42") (name "/PC3") (class "Default")
      (node (ref "P5") (pin "7") (pinfunction "7_7") (pintype "passive"))
      (node (ref "P5") (pin "8") (pinfunction "8_8") (pintype "passive"))
      (node (ref "U1") (pin "11") (pinfunction "PC3/IN13_11") (pintype "passive"))
    )
    (net (code "43") (name "/PC5") (class "Default")
      (node (ref "J3") (pin "1") (pinfunction "1_1") (pintype "passive"))
      (node (ref "K3") (pin "2") (pinfunction "2_2") (pintype "passive"))
      (node (ref "P5") (pin "11") (pinfunction "11_11") (pintype "passive"))
      (node (ref "P5") (pin "12") (pinfunction "12_12") (pintype "passive"))
      (node (ref "U1") (pin "25") (pinfunction "PC5/IN15_25") (pintype "passive"))
    )
    (net (code "44") (name "/PC7") (class "Default")
      (node (ref "P24") (pin "5") (pinfunction "5_5") (pintype "passive"))
      (node (ref "P24") (pin "6") (pinfunction "6_6") (pintype "passive"))
      (node (ref "U1") (pin "38") (pinfunction "MCK3/SDIO7/PC7_38") (pintype "passive"))
    )
    (net (code "45") (name "/PC8") (class "Default")
      (node (ref "P24") (pin "3") (pinfunction "3_3") (pintype "passive"))
      (node (ref "P24") (pin "4") (pinfunction "4_4") (pintype "passive"))
      (node (ref "R19") (pin "2") (pinfunction "2_2") (pintype "passive"))
      (node (ref "SD1") (pin "7") (pinfunction "7_7") (pintype "passive"))
      (node (ref "U1") (pin "39") (pinfunction "SDIO0/T8C3/PC8_39") (pintype "passive"))
    )
    (net (code "46") (name "/PC9") (class "Default")
      (node (ref "P24") (pin "1") (pinfunction "1_1") (pintype "passive"))
      (node (ref "P24") (pin "2") (pinfunction "2_2") (pintype "passive"))
      (node (ref "R18") (pin "2") (pinfunction "2_2") (pintype "passive"))
      (node (ref "SD1") (pin "8") (pinfunction "8_8") (pintype "passive"))
      (node (ref "U1") (pin "40") (pinfunction "SDIO1/T8C4PC9_40") (pintype "passive"))
    )
    (net (code "47") (name "/PC10") (class "Default")
      (node (ref "P5") (pin "13") (pinfunction "13_13") (pintype "passive"))
      (node (ref "P5") (pin "14") (pinfunction "14_14") (pintype "passive"))
      (node (ref "R20") (pin "2") (pinfunction "2_2") (pintype "passive"))
      (node (ref "SD1") (pin "9") (pinfunction "9_9") (pintype "passive"))
      (node (ref "U1") (pin "51") (pinfunction "TXD4/SDIO2/PC10_51") (pintype "passive"))
    )
    (net (code "48") (name "/PC11") (class "Default")
      (node (ref "P5") (pin "15") (pinfunction "15_15") (pintype "passive"))
      (node (ref "P5") (pin "16") (pinfunction "16_16") (pintype "passive"))
      (node (ref "R22") (pin "2") (pinfunction "2_2") (pintype "passive"))
      (node (ref "SD1") (pin "1") (pinfunction "1_1") (pintype "passive"))
      (node (ref "U1") (pin "52") (pinfunction "RXD4/SDIO3/PC11_52") (pintype "passive"))
    )
    (net (code "49") (name "/PC12") (class "Default")
      (node (ref "P5") (pin "17") (pinfunction "17_17") (pintype "passive"))
      (node (ref "P5") (pin "18") (pinfunction "18_18") (pintype "passive"))
      (node (ref "SD1") (pin "5") (pinfunction "5_5") (pintype "passive"))
      (node (ref "U1") (pin "53") (pinfunction "TXD5/SDCK/PC12_53") (pintype "passive"))
    )
    (net (code "50") (name "/PC13") (class "Default")
      (node (ref "P5") (pin "19") (pinfunction "19_19") (pintype "passive"))
      (node (ref "P5") (pin "20") (pinfunction "20_20") (pintype "passive"))
      (node (ref "U1") (pin "2") (pinfunction "TAMPER-RTC/PC13_2") (pintype "passive"))
    )
    (net (code "51") (name "/PC14") (class "Default")
      (node (ref "C4") (pin "2") (pinfunction "2_2") (pintype "passive"))
      (node (ref "U1") (pin "3") (pinfunction "OSC32I/PC14_3") (pintype "passive"))
      (node (ref "Y1") (pin "1") (pinfunction "OSC1_1") (pintype "passive"))
    )
    (net (code "52") (name "/PC15") (class "Default")
      (node (ref "C5") (pin "2") (pinfunction "2_2") (pintype "passive"))
      (node (ref "U1") (pin "4") (pinfunction "OSC32O/PC15_4") (pintype "passive"))
      (node (ref "Y1") (pin "2") (pinfunction "OSC2_2") (pintype "passive"))
    )
    (net (code "53") (name "/PD2") (class "Default")
      (node (ref "P5") (pin "21") (pinfunction "21_21") (pintype "passive"))
      (node (ref "P5") (pin "22") (pinfunction "22_22") (pintype "passive"))
      (node (ref "R23") (pin "2") (pinfunction "2_2") (pintype "passive"))
      (node (ref "SD1") (pin "2") (pinfunction "2_2") (pintype "passive"))
      (node (ref "U1") (pin "54") (pinfunction "RXD5/SDCMD/PD2_54") (pintype "passive"))
    )
    (net (code "54") (name "/RESET") (class "Default")
      (node (ref "C2") (pin "1") (pinfunction "1_1") (pintype "passive"))
      (node (ref "D1") (pin "1") (pinfunction "A_1") (pintype "passive"))
      (node (ref "K1") (pin "1") (pinfunction "1_1") (pintype "passive"))
      (node (ref "R1") (pin "2") (pinfunction "2_2") (pintype "passive"))
      (node (ref "U1") (pin "7") (pinfunction "NRST_7") (pintype "passive"))
    )
    (net (code "55") (name "/RXD") (class "Default")
      (node (ref "P12") (pin "1") (pinfunction "1_1") (pintype "passive"))
      (node (ref "U8") (pin "2") (pinfunction "TX_2") (pintype "passive"))
    )
    (net (code "56") (name "/TXD") (class "Default")
      (node (ref "P12") (pin "2") (pinfunction "2_2") (pintype "passive"))
      (node (ref "U8") (pin "3") (pinfunction "RX_3") (pintype "passive"))
    )
    (net (code "57") (name "/VCC5V") (class "Default")
      (node (ref "C22") (pin "2") (pinfunction "2_2") (pintype "passive"))
      (node (ref "C3") (pin "2") (pinfunction "2_2") (pintype "passive"))
      (node (ref "C30") (pin "2") (pinfunction "2_2") (pintype "passive"))
      (node (ref "C31") (pin "2") (pinfunction "2_2") (pintype "passive"))
      (node (ref "F1") (pin "1") (pinfunction "1_1") (pintype "passive"))
      (node (ref "J3") (pin "4") (pinfunction "4_4") (pintype "passive"))
      (node (ref "U2") (pin "3") (pinfunction "VCC_3") (pintype "passive"))
      (node (ref "U7") (pin "3") (pinfunction "IN_3") (pintype "power_in"))
      (node (ref "U8") (pin "16") (pinfunction "VCC_16") (pintype "passive"))
    )
    (net (code "58") (name "GND") (class "Default")
      (node (ref "BT1") (pin "2") (pinfunction "-_2") (pintype "passive"))
      (node (ref "C1") (pin "2") (pinfunction "2_2") (pintype "passive"))
      (node (ref "C10") (pin "2") (pinfunction "2_2") (pintype "passive"))
      (node (ref "C12") (pin "2") (pinfunction "2_2") (pintype "passive"))
      (node (ref "C14") (pin "2") (pinfunction "2_2") (pintype "passive"))
      (node (ref "C15") (pin "2") (pinfunction "2_2") (pintype "passive"))
      (node (ref "C16") (pin "2") (pinfunction "2_2") (pintype "passive"))
      (node (ref "C17") (pin "2") (pinfunction "2_2") (pintype "passive"))
      (node (ref "C18") (pin "2") (pinfunction "2_2") (pintype "passive"))
      (node (ref "C19") (pin "2") (pinfunction "2_2") (pintype "passive"))
      (node (ref "C2") (pin "2") (pinfunction "2_2") (pintype "passive"))
      (node (ref "C20") (pin "1") (pinfunction "1_1") (pintype "passive"))
      (node (ref "C21") (pin "2") (pinfunction "2_2") (pintype "passive"))
      (node (ref "C22") (pin "1") (pinfunction "1_1") (pintype "passive"))
      (node (ref "C23") (pin "2") (pinfunction "2_2") (pintype "passive"))
      (node (ref "C24") (pin "2") (pinfunction "2_2") (pintype "passive"))
      (node (ref "C25") (pin "2") (pinfunction "2_2") (pintype "passive"))
      (node (ref "C26") (pin "2") (pinfunction "2_2") (pintype "passive"))
      (node (ref "C27") (pin "2") (pinfunction "2_2") (pintype "passive"))
      (node (ref "C28") (pin "1") (pinfunction "1_1") (pintype "passive"))
      (node (ref "C29") (pin "1") (pinfunction "1_1") (pintype "passive"))
      (node (ref "C3") (pin "1") (pinfunction "1_1") (pintype "passive"))
      (node (ref "C30") (pin "1") (pinfunction "1_1") (pintype "passive"))
      (node (ref "C31") (pin "1") (pinfunction "1_1") (pintype "passive"))
      (node (ref "C4") (pin "1") (pinfunction "1_1") (pintype "passive"))
      (node (ref "C5") (pin "1") (pinfunction "1_1") (pintype "passive"))
      (node (ref "C6") (pin "1") (pinfunction "1_1") (pintype "passive"))
      (node (ref "C7") (pin "1") (pinfunction "1_1") (pintype "passive"))
      (node (ref "C8") (pin "1") (pinfunction "1_1") (pintype "passive"))
      (node (ref "C9") (pin "1") (pinfunction "1_1") (pintype "passive"))
      (node (ref "J1") (pin "1") (pinfunction "GND_1") (pintype "passive"))
      (node (ref "J2") (pin "4") (pinfunction "GND_4") (pintype "passive"))
      (node (ref "J3") (pin "3") (pinfunction "3_3") (pintype "passive"))
      (node (ref "J4") (pin "4") (pinfunction "GND_4") (pintype "passive"))
      (node (ref "K1") (pin "2") (pinfunction "2_2") (pintype "passive"))
      (node (ref "K3") (pin "1") (pinfunction "1_1") (pintype "passive"))
      (node (ref "K4") (pin "1") (pinfunction "1_1") (pintype "passive"))
      (node (ref "LED3") (pin "2") (pinfunction "2_2") (pintype "passive"))
      (node (ref "P1") (pin "2") (pinfunction "2_2") (pintype "passive"))
      (node (ref "P10") (pin "1") (pinfunction "1_1") (pintype "passive"))
      (node (ref "P11") (pin "1") (pinfunction "1_1") (pintype "passive"))
      (node (ref "P14") (pin "8") (pinfunction "8_8") (pintype "passive"))
      (node (ref "P15") (pin "5") (pinfunction "5_5") (pintype "passive"))
      (node (ref "P15") (pin "6") (pinfunction "6_6") (pintype "passive"))
      (node (ref "P7") (pin "1") (pinfunction "1_1") (pintype "passive"))
      (node (ref "R10") (pin "1") (pinfunction "1_1") (pintype "passive"))
      (node (ref "R14") (pin "1") (pinfunction "1_1") (pintype "passive"))
      (node (ref "R7") (pin "1") (pinfunction "1_1") (pintype "passive"))
      (node (ref "SD1") (pin "3") (pinfunction "3_3") (pintype "passive"))
      (node (ref "SD1") (pin "6") (pinfunction "6_6") (pintype "passive"))
      (node (ref "SD2") (pin "3") (pinfunction "3_3") (pintype "passive"))
      (node (ref "SD2") (pin "6") (pinfunction "6_6") (pintype "passive"))
      (node (ref "U1") (pin "12") (pinfunction "VSSA_12") (pintype "passive"))
      (node (ref "U1") (pin "18") (pinfunction "VSS4_18") (pintype "passive"))
      (node (ref "U1") (pin "31") (pinfunction "VSS1_31") (pintype "passive"))
      (node (ref "U1") (pin "47") (pinfunction "VSS2_47") (pintype "passive"))
      (node (ref "U1") (pin "63") (pinfunction "VSS3_63") (pintype "passive"))
      (node (ref "U2") (pin "2") (pinfunction "GND_2") (pintype "passive"))
      (node (ref "U2") (pin "8") (pinfunction "RS_8") (pintype "passive"))
      (node (ref "U3") (pin "8") (pinfunction "AGND_8") (pintype "passive"))
      (node (ref "U4") (pin "8") (pinfunction "GND_8") (pintype "passive"))
      (node (ref "U5") (pin "1") (pinfunction "1_1") (pintype "passive"))
      (node (ref "U6") (pin "4") (pinfunction "GND_4") (pintype "passive"))
      (node (ref "U7") (pin "1") (pinfunction "GND_1") (pintype "power_in"))
      (node (ref "U8") (pin "1") (pinfunction "GND_1") (pintype "passive"))
    )
    (net (code "59") (name "Net-(BT1-+)") (class "Default")
      (node (ref "BT1") (pin "1") (pinfunction "+_1") (pintype "passive"))
      (node (ref "D2") (pin "1") (pinfunction "A_1") (pintype "passive"))
    )
    (net (code "60") (name "Net-(C11-Pad2)") (class "Default")
      (node (ref "C11") (pin "2") (pinfunction "2_2") (pintype "passive"))
      (node (ref "R4") (pin "2") (pinfunction "2_2") (pintype "passive"))
      (node (ref "R7") (pin "2") (pinfunction "2_2") (pintype "passive"))
    )
    (net (code "61") (name "Net-(C13-Pad2)") (class "Default")
      (node (ref "C13") (pin "2") (pinfunction "2_2") (pintype "passive"))
      (node (ref "R10") (pin "2") (pinfunction "2_2") (pintype "passive"))
      (node (ref "R9") (pin "1") (pinfunction "1_1") (pintype "passive"))
    )
    (net (code "62") (name "Net-(D1-K)") (class "Default")
      (node (ref "D1") (pin "2") (pinfunction "K_2") (pintype "passive"))
      (node (ref "Q2") (pin "1") (pinfunction "C_1") (pintype "passive"))
      (node (ref "R32") (pin "2") (pinfunction "2_2") (pintype "passive"))
    )
    (net (code "63") (name "Net-(D2-K)") (class "Default")
      (node (ref "D2") (pin "2") (pinfunction "K_2") (pintype "passive"))
      (node (ref "D3") (pin "2") (pinfunction "K_2") (pintype "passive"))
      (node (ref "U1") (pin "1") (pinfunction "VBAT_1") (pintype "passive"))
    )
    (net (code "64") (name "Net-(J1-L)") (class "Default")
      (node (ref "C17") (pin "1") (pinfunction "1_1") (pintype "passive"))
      (node (ref "J1") (pin "2") (pinfunction "L_2") (pintype "passive"))
      (node (ref "R9") (pin "2") (pinfunction "2_2") (pintype "passive"))
    )
    (net (code "65") (name "Net-(J1-R)") (class "Default")
      (node (ref "C18") (pin "1") (pinfunction "1_1") (pintype "passive"))
      (node (ref "J1") (pin "3") (pinfunction "R_3") (pintype "passive"))
      (node (ref "R4") (pin "1") (pinfunction "1_1") (pintype "passive"))
    )
    (net (code "66") (name "Net-(J2-DATA+)") (class "Default")
      (node (ref "J2") (pin "3") (pinfunction "DATA+_3") (pintype "passive"))
      (node (ref "R5") (pin "2") (pinfunction "2_2") (pintype "passive"))
      (node (ref "R6") (pin "2") (pinfunction "2_2") (pintype "passive"))
    )
    (net (code "67") (name "Net-(J2-DATA-)") (class "Default")
      (node (ref "J2") (pin "2") (pinfunction "DATA-_2") (pintype "passive"))
      (node (ref "R8") (pin "2") (pinfunction "2_2") (pintype "passive"))
    )
    (net (code "68") (name "Net-(J4-DATA+)") (class "Default")
      (node (ref "J4") (pin "3") (pinfunction "DATA+_3") (pintype "passive"))
      (node (ref "R28") (pin "1") (pinfunction "1_1") (pintype "passive"))
      (node (ref "U8") (pin "5") (pinfunction "D+_5") (pintype "passive"))
    )
    (net (code "69") (name "Net-(J4-DATA-)") (class "Default")
      (node (ref "J4") (pin "2") (pinfunction "DATA-_2") (pintype "passive"))
      (node (ref "U8") (pin "6") (pinfunction "D-_6") (pintype "passive"))
    )
    (net (code "70") (name "Net-(LED1-Pad1)") (class "Default")
      (node (ref "LED1") (pin "1") (pinfunction "1_1") (pintype "passive"))
      (node (ref "R15") (pin "2") (pinfunction "2_2") (pintype "passive"))
    )
    (net (code "71") (name "Net-(LED2-Pad1)") (class "Default")
      (node (ref "LED2") (pin "1") (pinfunction "1_1") (pintype "passive"))
      (node (ref "R17") (pin "2") (pinfunction "2_2") (pintype "passive"))
    )
    (net (code "72") (name "Net-(LED3-Pad1)") (class "Default")
      (node (ref "LED3") (pin "1") (pinfunction "1_1") (pintype "passive"))
      (node (ref "R21") (pin "2") (pinfunction "2_2") (pintype "passive"))
    )
    (net (code "73") (name "Net-(P15-Pad3)") (class "Default")
      (node (ref "P15") (pin "3") (pinfunction "3_3") (pintype "passive"))
      (node (ref "R12") (pin "2") (pinfunction "2_2") (pintype "passive"))
    )
    (net (code "74") (name "Net-(P15-Pad4)") (class "Default")
      (node (ref "P15") (pin "4") (pinfunction "4_4") (pintype "passive"))
      (node (ref "R13") (pin "1") (pinfunction "1_1") (pintype "passive"))
    )
    (net (code "75") (name "Net-(Q1-B)") (class "Default")
      (node (ref "Q1") (pin "2") (pinfunction "B_2") (pintype "passive"))
      (node (ref "R30") (pin "1") (pinfunction "1_1") (pintype "passive"))
    )
    (net (code "76") (name "Net-(Q1-C)") (class "Default")
      (node (ref "Q1") (pin "1") (pinfunction "C_1") (pintype "passive"))
      (node (ref "R25") (pin "1") (pinfunction "1_1") (pintype "passive"))
    )
    (net (code "77") (name "Net-(Q2-B)") (class "Default")
      (node (ref "Q2") (pin "2") (pinfunction "B_2") (pintype "passive"))
      (node (ref "R31") (pin "1") (pinfunction "1_1") (pintype "passive"))
    )
    (net (code "78") (name "Net-(Q2-E)") (class "Default")
      (node (ref "Q2") (pin "3") (pinfunction "E_3") (pintype "passive"))
      (node (ref "R30") (pin "2") (pinfunction "2_2") (pintype "passive"))
      (node (ref "U8") (pin "14") (pinfunction "RTS#_14") (pintype "passive"))
    )
    (net (code "79") (name "Net-(R16-Pad1)") (class "Default")
      (node (ref "R16") (pin "1") (pinfunction "1_1") (pintype "passive"))
      (node (ref "U5") (pin "8") (pinfunction "8_8") (pintype "passive"))
    )
    (net (code "80") (name "Net-(U1-OSCI)") (class "Default")
      (node (ref "C6") (pin "2") (pinfunction "2_2") (pintype "passive"))
      (node (ref "R3") (pin "1") (pinfunction "1_1") (pintype "passive"))
      (node (ref "U1") (pin "5") (pinfunction "OSCI_5") (pintype "passive"))
      (node (ref "Y2") (pin "1") (pinfunction "OSC1_1") (pintype "passive"))
    )
    (net (code "81") (name "Net-(U1-OSCO)") (class "Default")
      (node (ref "C7") (pin "2") (pinfunction "2_2") (pintype "passive"))
      (node (ref "R3") (pin "2") (pinfunction "2_2") (pintype "passive"))
      (node (ref "U1") (pin "6") (pinfunction "OSCO_6") (pintype "passive"))
      (node (ref "Y2") (pin "2") (pinfunction "OSC2_2") (pintype "passive"))
    )
    (net (code "82") (name "Net-(U2-CANH)") (class "Default")
      (node (ref "P2") (pin "1") (pinfunction "1_1") (pintype "passive"))
      (node (ref "R2") (pin "1") (pinfunction "1_1") (pintype "passive"))
      (node (ref "U2") (pin "7") (pinfunction "CANH_7") (pintype "passive"))
    )
    (net (code "83") (name "Net-(U2-CANL)") (class "Default")
      (node (ref "P2") (pin "2") (pinfunction "2_2") (pintype "passive"))
      (node (ref "R2") (pin "2") (pinfunction "2_2") (pintype "passive"))
      (node (ref "U2") (pin "6") (pinfunction "CANL_6") (pintype "passive"))
    )
    (net (code "84") (name "Net-(U3-AOUTL)") (class "Default")
      (node (ref "C13") (pin "1") (pinfunction "1_1") (pintype "passive"))
      (node (ref "U3") (pin "7") (pinfunction "AOUTL_7") (pintype "passive"))
    )
    (net (code "85") (name "Net-(U3-AOUTR)") (class "Default")
      (node (ref "C11") (pin "1") (pinfunction "1_1") (pintype "passive"))
      (node (ref "U3") (pin "10") (pinfunction "AOUTR_10") (pintype "passive"))
    )
    (net (code "86") (name "Net-(U3-FILT+)") (class "Default")
      (node (ref "C14") (pin "1") (pinfunction "1_1") (pintype "passive"))
      (node (ref "U3") (pin "6") (pinfunction "FILT+_6") (pintype "passive"))
    )
    (net (code "87") (name "Net-(U3-VQ)") (class "Default")
      (node (ref "C15") (pin "1") (pinfunction "1_1") (pintype "passive"))
      (node (ref "C16") (pin "1") (pinfunction "1_1") (pintype "passive"))
      (node (ref "U3") (pin "5") (pinfunction "VQ_5") (pintype "passive"))
    )
    (net (code "88") (name "Net-(U4-ADC)") (class "Default")
      (node (ref "P13") (pin "7") (pinfunction "7_7") (pintype "passive"))
      (node (ref "U4") (pin "21") (pinfunction "ADC_21") (pintype "passive"))
    )
    (net (code "89") (name "Net-(U4-CS0)") (class "Default")
      (node (ref "P16") (pin "6") (pinfunction "6_6") (pintype "passive"))
      (node (ref "U4") (pin "14") (pinfunction "CS0_14") (pintype "passive"))
    )
    (net (code "90") (name "Net-(U4-EN)") (class "Default")
      (node (ref "P13") (pin "6") (pinfunction "6_6") (pintype "passive"))
      (node (ref "R11") (pin "2") (pinfunction "2_2") (pintype "passive"))
      (node (ref "U4") (pin "20") (pinfunction "EN_20") (pintype "passive"))
    )
    (net (code "91") (name "Net-(U4-IO0)") (class "Default")
      (node (ref "P14") (pin "5") (pinfunction "5_5") (pintype "passive"))
      (node (ref "U4") (pin "5") (pinfunction "IO0_5") (pintype "passive"))
    )
    (net (code "92") (name "Net-(U4-IO2)") (class "Default")
      (node (ref "P14") (pin "6") (pinfunction "6_6") (pintype "passive"))
      (node (ref "U4") (pin "6") (pinfunction "IO2_6") (pintype "passive"))
    )
    (net (code "93") (name "Net-(U4-IO4)") (class "Default")
      (node (ref "P14") (pin "4") (pinfunction "4_4") (pintype "passive"))
      (node (ref "U4") (pin "4") (pinfunction "IO4_4") (pintype "passive"))
    )
    (net (code "94") (name "Net-(U4-IO5)") (class "Default")
      (node (ref "P14") (pin "3") (pinfunction "3_3") (pintype "passive"))
      (node (ref "U4") (pin "3") (pinfunction "IO5_3") (pintype "passive"))
    )
    (net (code "95") (name "Net-(U4-IO9)") (class "Default")
      (node (ref "P16") (pin "4") (pinfunction "4_4") (pintype "passive"))
      (node (ref "U4") (pin "12") (pinfunction "IO9_12") (pintype "passive"))
    )
    (net (code "96") (name "Net-(U4-IO10)") (class "Default")
      (node (ref "P16") (pin "3") (pinfunction "3_3") (pintype "passive"))
      (node (ref "U4") (pin "11") (pinfunction "IO10_11") (pintype "passive"))
    )
    (net (code "97") (name "Net-(U4-IO12)") (class "Default")
      (node (ref "P13") (pin "3") (pinfunction "3_3") (pintype "passive"))
      (node (ref "U4") (pin "17") (pinfunction "IO12_17") (pintype "passive"))
    )
    (net (code "98") (name "Net-(U4-IO13)") (class "Default")
      (node (ref "P13") (pin "2") (pinfunction "2_2") (pintype "passive"))
      (node (ref "U4") (pin "16") (pinfunction "IO13_16") (pintype "passive"))
    )
    (net (code "99") (name "Net-(U4-IO14)") (class "Default")
      (node (ref "P13") (pin "4") (pinfunction "4_4") (pintype "passive"))
      (node (ref "U4") (pin "18") (pinfunction "IO14_18") (pintype "passive"))
    )
    (net (code "100") (name "Net-(U4-IO15)") (class "Default")
      (node (ref "P14") (pin "7") (pinfunction "7_7") (pintype "passive"))
      (node (ref "R14") (pin "2") (pinfunction "2_2") (pintype "passive"))
      (node (ref "U4") (pin "7") (pinfunction "IO15_7") (pintype "passive"))
    )
    (net (code "101") (name "Net-(U4-IO16)") (class "Default")
      (node (ref "P13") (pin "5") (pinfunction "5_5") (pintype "passive"))
      (node (ref "U4") (pin "19") (pinfunction "IO16_19") (pintype "passive"))
    )
    (net (code "102") (name "Net-(U4-MISO)") (class "Default")
      (node (ref "P16") (pin "5") (pinfunction "5_5") (pintype "passive"))
      (node (ref "U4") (pin "13") (pinfunction "MISO_13") (pintype "passive"))
    )
    (net (code "103") (name "Net-(U4-MOSI)") (class "Default")
      (node (ref "P16") (pin "2") (pinfunction "2_2") (pintype "passive"))
      (node (ref "U4") (pin "10") (pinfunction "MOSI_10") (pintype "passive"))
    )
    (net (code "104") (name "Net-(U4-RST)") (class "Default")
      (node (ref "P13") (pin "8") (pinfunction "8_8") (pintype "passive"))
      (node (ref "U4") (pin "22") (pinfunction "RST_22") (pintype "passive"))
    )
    (net (code "105") (name "Net-(U4-SCLCK)") (class "Default")
      (node (ref "P16") (pin "1") (pinfunction "1_1") (pintype "passive"))
      (node (ref "U4") (pin "9") (pinfunction "SCLCK_9") (pintype "passive"))
    )
    (net (code "106") (name "Net-(U8-DTR#)") (class "Default")
      (node (ref "R31") (pin "2") (pinfunction "2_2") (pintype "passive"))
      (node (ref "U8") (pin "13") (pinfunction "DTR#_13") (pintype "passive"))
    )
    (net (code "107") (name "Net-(U8-V3)") (class "Default")
      (node (ref "C26") (pin "1") (pinfunction "1_1") (pintype "passive"))
      (node (ref "U8") (pin "4") (pinfunction "V3_4") (pintype "passive"))
    )
    (net (code "108") (name "Net-(U8-X0)") (class "Default")
      (node (ref "C28") (pin "2") (pinfunction "2_2") (pintype "passive"))
      (node (ref "U8") (pin "8") (pinfunction "X0_8") (pintype "passive"))
      (node (ref "Y3") (pin "1") (pinfunction "OSC1_1") (pintype "passive"))
    )
    (net (code "109") (name "Net-(U8-XI)") (class "Default")
      (node (ref "C29") (pin "2") (pinfunction "2_2") (pintype "passive"))
      (node (ref "U8") (pin "7") (pinfunction "XI_7") (pintype "passive"))
      (node (ref "Y3") (pin "2") (pinfunction "OSC2_2") (pintype "passive"))
    )
    (net (code "110") (name "VCC") (class "Default")
      (node (ref "C1") (pin "1") (pinfunction "1_1") (pintype "passive"))
      (node (ref "C10") (pin "1") (pinfunction "1_1") (pintype "passive"))
      (node (ref "C12") (pin "1") (pinfunction "1_1") (pintype "passive"))
      (node (ref "C19") (pin "1") (pinfunction "1_1") (pintype "passive"))
      (node (ref "C20") (pin "2") (pinfunction "2_2") (pintype "passive"))
      (node (ref "C21") (pin "1") (pinfunction "1_1") (pintype "passive"))
      (node (ref "C23") (pin "1") (pinfunction "1_1") (pintype "passive"))
      (node (ref "C24") (pin "1") (pinfunction "1_1") (pintype "passive"))
      (node (ref "C25") (pin "1") (pinfunction "1_1") (pintype "passive"))
      (node (ref "C27") (pin "1") (pinfunction "1_1") (pintype "passive"))
      (node (ref "C8") (pin "2") (pinfunction "2_2") (pintype "passive"))
      (node (ref "C9") (pin "2") (pinfunction "2_2") (pintype "passive"))
      (node (ref "D3") (pin "1") (pinfunction "A_1") (pintype "passive"))
      (node (ref "K2") (pin "1") (pinfunction "1_1") (pintype "passive"))
      (node (ref "P1") (pin "1") (pinfunction "1_1") (pintype "passive"))
      (node (ref "P11") (pin "4") (pinfunction "4_4") (pintype "passive"))
      (node (ref "P13") (pin "1") (pinfunction "1_1") (pintype "passive"))
      (node (ref "P15") (pin "1") (pinfunction "1_1") (pintype "passive"))
      (node (ref "P15") (pin "2") (pinfunction "2_2") (pintype "passive"))
      (node (ref "Q1") (pin "3") (pinfunction "E_3") (pintype "passive"))
      (node (ref "R1") (pin "1") (pinfunction "1_1") (pintype "passive"))
      (node (ref "R11") (pin "1") (pinfunction "1_1") (pintype "passive"))
      (node (ref "R15") (pin "1") (pinfunction "1_1") (pintype "passive"))
      (node (ref "R17") (pin "1") (pinfunction "1_1") (pintype "passive"))
      (node (ref "R18") (pin "1") (pinfunction "1_1") (pintype "passive"))
      (node (ref "R19") (pin "1") (pinfunction "1_1") (pintype "passive"))
      (node (ref "R20") (pin "1") (pinfunction "1_1") (pintype "passive"))
      (node (ref "R21") (pin "1") (pinfunction "1_1") (pintype "passive"))
      (node (ref "R22") (pin "1") (pinfunction "1_1") (pintype "passive"))
      (node (ref "R23") (pin "1") (pinfunction "1_1") (pintype "passive"))
      (node (ref "R24") (pin "1") (pinfunction "1_1") (pintype "passive"))
      (node (ref "R26") (pin "1") (pinfunction "1_1") (pintype "passive"))
      (node (ref "R27") (pin "1") (pinfunction "1_1") (pintype "passive"))
      (node (ref "R28") (pin "2") (pinfunction "2_2") (pintype "passive"))
      (node (ref "R29") (pin "1") (pinfunction "1_1") (pintype "passive"))
      (node (ref "R32") (pin "1") (pinfunction "1_1") (pintype "passive"))
      (node (ref "R5") (pin "1") (pinfunction "1_1") (pintype "passive"))
      (node (ref "SD1") (pin "4") (pinfunction "4_4") (pintype "passive"))
      (node (ref "SD2") (pin "4") (pinfunction "4_4") (pintype "passive"))
      (node (ref "U1") (pin "13") (pinfunction "VDDA_13") (pintype "passive"))
      (node (ref "U1") (pin "19") (pinfunction "VDD4_19") (pintype "passive"))
      (node (ref "U1") (pin "32") (pinfunction "VDD1_32") (pintype "passive"))
      (node (ref "U1") (pin "48") (pinfunction "VDD2_48") (pintype "passive"))
      (node (ref "U1") (pin "64") (pinfunction "VDD3_64") (pintype "passive"))
      (node (ref "U3") (pin "9") (pinfunction "VCC_9") (pintype "passive"))
      (node (ref "U4") (pin "15") (pinfunction "VCC_15") (pintype "passive"))
      (node (ref "U5") (pin "2") (pinfunction "2_2") (pintype "passive"))
      (node (ref "U6") (pin "3") (pinfunction "WP#_3") (pintype "passive"))
      (node (ref "U6") (pin "7") (pinfunction "HOLD_7") (pintype "passive"))
      (node (ref "U6") (pin "8") (pinfunction "VCC_8") (pintype "passive"))
      (node (ref "U7") (pin "2") (pinfunction "OUT_2") (pintype "power_in"))
      (node (ref "U7") (pin "4") (pinfunction "OUT_4") (pintype "power_in"))
    )
    (net (code "111") (name "unconnected-(J3-Pad2)") (class "Default")
      (node (ref "J3") (pin "2") (pinfunction "2_2") (pintype "passive"))
    )
    (net (code "112") (name "unconnected-(J3-Pad6)") (class "Default")
      (node (ref "J3") (pin "6") (pinfunction "6_6") (pintype "passive"))
    )
    (net (code "113") (name "unconnected-(SD2-Pad8)") (class "Default")
      (node (ref "SD2") (pin "8") (pinfunction "8_8") (pintype "passive"))
    )
    (net (code "114") (name "unconnected-(SD2-Pad9)") (class "Default")
      (node (ref "SD2") (pin "9") (pinfunction "9_9") (pintype "passive"))
    )
    (net (code "115") (name "unconnected-(U2-VREF-Pad5)") (class "Default")
      (node (ref "U2") (pin "5") (pinfunction "VREF_5") (pintype "passive"))
    )
    (net (code "116") (name "unconnected-(U8-Pad9)") (class "Default")
      (node (ref "U8") (pin "9") (pinfunction "9_9") (pintype "passive"))
    )
    (net (code "117") (name "unconnected-(U8-Pad10)") (class "Default")
      (node (ref "U8") (pin "10") (pinfunction "10_10") (pintype "passive"))
    )
    (net (code "118") (name "unconnected-(U8-Pad11)") (class "Default")
      (node (ref "U8") (pin "11") (pinfunction "11_11") (pintype "passive"))
    )
    (net (code "119") (name "unconnected-(U8-Pad12)") (class "Default")
      (node (ref "U8") (pin "12") (pinfunction "12_12") (pintype "passive"))
    )
    (net (code "120") (name "unconnected-(U8-Pad15)") (class "Default")
      (node (ref "U8") (pin "15") (pinfunction "15_15") (pintype "passive"))
    )
  )
)
